# WeightAlarm.net
KiCad netlist of a schematic drawn in EAGLE
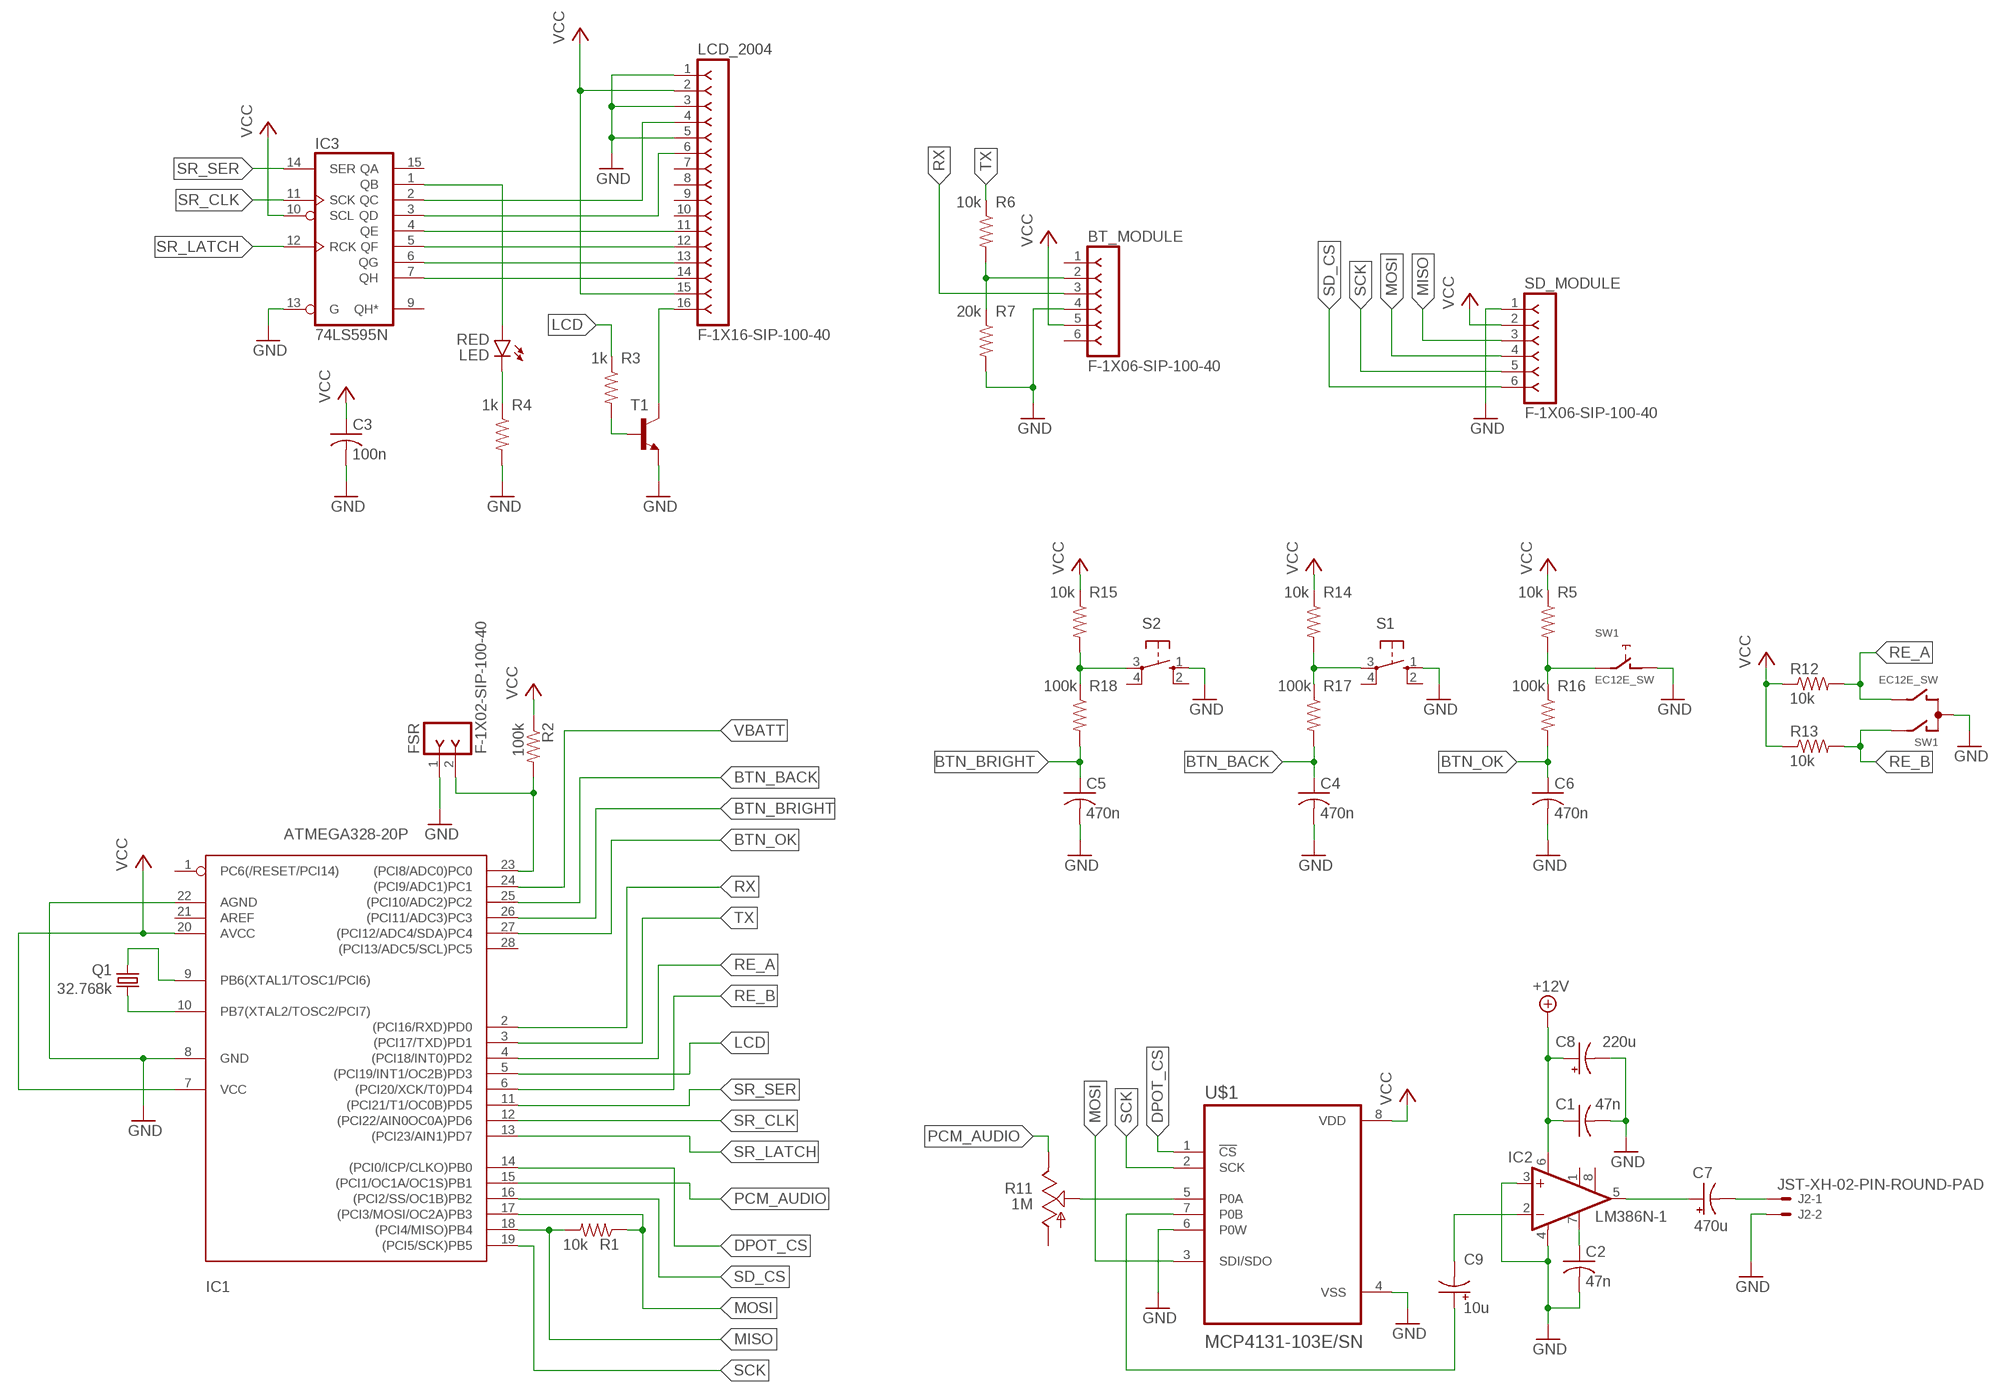
[diagram p0: schematic, sheet 1]

(export (version "E")
  (design (tool "Eeschema 10.0.6"))
  (components
    (comp (ref "BT_MODULE")
      (value "F-1X06-SIP-100-40")
      (footprint "eagle-import:SIP-100-06-40")
      (libsource (lib "eagle-import") (part "F-1X06-SIP-100-40"))
    )
    (comp (ref "C1")
      (value "47n")
      (footprint "eagle-import:C025-030X050")
      (libsource (lib "eagle-import") (part "C-US025-030X050"))
    )
    (comp (ref "C2")
      (value "47n")
      (footprint "eagle-import:C025-030X050")
      (libsource (lib "eagle-import") (part "C-US025-030X050"))
    )
    (comp (ref "C3")
      (value "100n")
      (footprint "eagle-import:C025-030X050")
      (libsource (lib "eagle-import") (part "C-US025-030X050"))
    )
    (comp (ref "C4")
      (value "470n")
      (footprint "eagle-import:C025-030X050")
      (libsource (lib "eagle-import") (part "C-US025-030X050"))
    )
    (comp (ref "C5")
      (value "470n")
      (footprint "eagle-import:C025-030X050")
      (libsource (lib "eagle-import") (part "C-US025-030X050"))
    )
    (comp (ref "C6")
      (value "470n")
      (footprint "eagle-import:C025-030X050")
      (libsource (lib "eagle-import") (part "C-US025-030X050"))
    )
    (comp (ref "C7")
      (value "470u")
      (footprint "eagle-import:E2,5-7")
      (libsource (lib "eagle-import") (part "CPOL-USE2.5-7"))
    )
    (comp (ref "C8")
      (value "220u")
      (footprint "eagle-import:E2,5-6")
      (libsource (lib "eagle-import") (part "CPOL-USE2.5-6"))
    )
    (comp (ref "C9")
      (value "10u")
      (footprint "eagle-import:E2,5-5")
      (libsource (lib "eagle-import") (part "CPOL-USE2.5-5"))
    )
    (comp (ref "FSR")
      (value "F-1X02-SIP-100-40")
      (footprint "eagle-import:SIP-100-02-40")
      (libsource (lib "eagle-import") (part "F-1X02-SIP-100-40"))
    )
    (comp (ref "IC1")
      (value "ATMEGA328-20P")
      (footprint "eagle-import:DIL28-3")
      (libsource (lib "eagle-import") (part "ATMEGA328P-20"))
    )
    (comp (ref "IC2")
      (value "LM386N-1")
      (footprint "eagle-import:DIL08")
      (libsource (lib "eagle-import") (part "LM386?-N1"))
    )
    (comp (ref "IC3")
      (value "74LS595N")
      (footprint "eagle-import:DIL16")
      (fields (field (name "SPICEPREFIX") "X"))
      (libsource (lib "eagle-import") (part "74595NLS"))
    )
    (comp (ref "J2")
      (value "JST-XH-02-PIN-ROUND-PAD")
      (footprint "eagle-import:JST-XH-02-PACKAGE-ROUND-PAD")
      (libsource (lib "eagle-import") (part "JST-XH-02-PIN-ROUND-PAD"))
    )
    (comp (ref "LCD_2004")
      (value "F-1X16-SIP-100-40")
      (footprint "eagle-import:SIP-100-16-40")
      (fields (field (name "SPICEPREFIX") "X"))
      (libsource (lib "eagle-import") (part "F-1X16-SIP-100-40"))
    )
    (comp (ref "LED")
      (value "RED")
      (footprint "eagle-import:LED5MM")
      (fields (field (name "SPICEPREFIX") "L"))
      (libsource (lib "eagle-import") (part "LED5MM"))
    )
    (comp (ref "Q1")
      (value "32.768k")
      (footprint "eagle-import:TC26V")
      (libsource (lib "eagle-import") (part "CRYSTALTC26V"))
    )
    (comp (ref "R1")
      (value "10k")
      (footprint "eagle-import:0207_7")
      (libsource (lib "eagle-import") (part "R-US_0207/7"))
    )
    (comp (ref "R2")
      (value "100k")
      (footprint "eagle-import:0207_7")
      (libsource (lib "eagle-import") (part "R-US_0207/7"))
    )
    (comp (ref "R3")
      (value "1k")
      (footprint "eagle-import:0207_7")
      (libsource (lib "eagle-import") (part "R-US_0207/7"))
    )
    (comp (ref "R4")
      (value "1k")
      (footprint "eagle-import:0207_7")
      (libsource (lib "eagle-import") (part "R-US_0207/7"))
    )
    (comp (ref "R5")
      (value "10k")
      (footprint "eagle-import:0207_7")
      (libsource (lib "eagle-import") (part "R-US_0207/7"))
    )
    (comp (ref "R6")
      (value "10k")
      (footprint "eagle-import:0207_7")
      (libsource (lib "eagle-import") (part "R-US_0207/7"))
    )
    (comp (ref "R7")
      (value "20k")
      (footprint "eagle-import:0207_7")
      (libsource (lib "eagle-import") (part "R-US_0207/7"))
    )
    (comp (ref "R11")
      (value "1M")
      (footprint "eagle-import:B25P")
      (libsource (lib "eagle-import") (part "TRIM_US-B25P"))
    )
    (comp (ref "R12")
      (value "10k")
      (footprint "eagle-import:0207_7")
      (libsource (lib "eagle-import") (part "R-US_0207/7"))
    )
    (comp (ref "R13")
      (value "10k")
      (footprint "eagle-import:0207_7")
      (libsource (lib "eagle-import") (part "R-US_0207/7"))
    )
    (comp (ref "R14")
      (value "10k")
      (footprint "eagle-import:0207_7")
      (libsource (lib "eagle-import") (part "R-US_0207/7"))
    )
    (comp (ref "R15")
      (value "10k")
      (footprint "eagle-import:0207_7")
      (libsource (lib "eagle-import") (part "R-US_0207/7"))
    )
    (comp (ref "R16")
      (value "100k")
      (footprint "eagle-import:0207_7")
      (libsource (lib "eagle-import") (part "R-US_0207/7"))
    )
    (comp (ref "R17")
      (value "100k")
      (footprint "eagle-import:0207_7")
      (libsource (lib "eagle-import") (part "R-US_0207/7"))
    )
    (comp (ref "R18")
      (value "100k")
      (footprint "eagle-import:0207_7")
      (libsource (lib "eagle-import") (part "R-US_0207/7"))
    )
    (comp (ref "S1")
      (value "10-XX")
      (footprint "eagle-import:B3F-10XX")
      (fields (field (name "MPN") "B3F-1000"))
      (libsource (lib "eagle-import") (part "10-XX"))
    )
    (comp (ref "S2")
      (value "10-XX")
      (footprint "eagle-import:B3F-10XX")
      (fields (field (name "MPN") "B3F-1000"))
      (libsource (lib "eagle-import") (part "10-XX"))
    )
    (comp (ref "SD_MODULE")
      (value "F-1X06-SIP-100-40")
      (footprint "eagle-import:SIP-100-06-40")
      (libsource (lib "eagle-import") (part "F-1X06-SIP-100-40"))
    )
    (comp (ref "SW1")
      (value "EC12E_SW")
      (footprint "eagle-import:ALPS_EC12E_SW")
      (fields (field (name "MPN") "EC12E2424407"))
      (libsource (lib "eagle-import") (part "EC12E_SW"))
    )
    (comp (ref "T1")
      (value "-NPN-TO92-EBC")
      (footprint "eagle-import:TO92-EBC")
      (fields (field (name "SPICEPREFIX") "J"))
      (libsource (lib "eagle-import") (part "-NPN-TO92-EBC"))
    )
    (comp (ref "U$1")
      (value "MCP4131-103E/SN")
      (footprint "eagle-import:SOIC127P599X175-8N")
      (fields (field (name "MF") "Microchip"))
      (libsource (lib "eagle-import") (part "MCP4131-103E/SN"))
    )
  )
  (nets
    (net (code "1") (name "+12V") (class "Default")
      (node (ref "C1") (pin "1") (pinfunction "1_1") (pintype "passive"))
      (node (ref "C8") (pin "+") (pinfunction "+_+") (pintype "passive"))
      (node (ref "IC2") (pin "6") (pinfunction "VS_6") (pintype "power_in"))
    )
    (net (code "2") (name "BTN_BACK") (class "Default")
      (node (ref "C4") (pin "1") (pinfunction "1_1") (pintype "passive"))
      (node (ref "IC1") (pin "25") (pinfunction "(PCI10/ADC2)PC2_25") (pintype "bidirectional"))
      (node (ref "R17") (pin "2") (pinfunction "2_2") (pintype "passive"))
    )
    (net (code "3") (name "BTN_BRIGHT") (class "Default")
      (node (ref "C5") (pin "1") (pinfunction "1_1") (pintype "passive"))
      (node (ref "IC1") (pin "26") (pinfunction "(PCI11/ADC3)PC3_26") (pintype "bidirectional"))
      (node (ref "R18") (pin "2") (pinfunction "2_2") (pintype "passive"))
    )
    (net (code "4") (name "BTN_OK") (class "Default")
      (node (ref "C6") (pin "1") (pinfunction "1_1") (pintype "passive"))
      (node (ref "IC1") (pin "27") (pinfunction "(PCI12/ADC4/SDA)PC4_27") (pintype "bidirectional"))
      (node (ref "R16") (pin "2") (pinfunction "2_2") (pintype "passive"))
    )
    (net (code "5") (name "DPOT_CS") (class "Default")
      (node (ref "IC1") (pin "14") (pinfunction "(PCI0/ICP/CLKO)PB0_14") (pintype "bidirectional"))
      (node (ref "U$1") (pin "1") (pinfunction "~{CS}_1") (pintype "input"))
    )
    (net (code "6") (name "GND") (class "Default")
      (node (ref "BT_MODULE") (pin "4") (pinfunction "4_4") (pintype "passive"))
      (node (ref "C1") (pin "2") (pinfunction "2_2") (pintype "passive"))
      (node (ref "C2") (pin "2") (pinfunction "2_2") (pintype "passive"))
      (node (ref "C3") (pin "2") (pinfunction "2_2") (pintype "passive"))
      (node (ref "C4") (pin "2") (pinfunction "2_2") (pintype "passive"))
      (node (ref "C5") (pin "2") (pinfunction "2_2") (pintype "passive"))
      (node (ref "C6") (pin "2") (pinfunction "2_2") (pintype "passive"))
      (node (ref "C8") (pin "-") (pinfunction "-_-") (pintype "passive"))
      (node (ref "FSR") (pin "1") (pinfunction "1_1") (pintype "passive"))
      (node (ref "IC1") (pin "22") (pinfunction "AGND_22") (pintype "bidirectional"))
      (node (ref "IC1") (pin "8") (pinfunction "GND_8") (pintype "bidirectional"))
      (node (ref "IC2") (pin "3") (pinfunction "+IN_3") (pintype "input"))
      (node (ref "IC2") (pin "4") (pinfunction "GND_4") (pintype "power_in"))
      (node (ref "IC3") (pin "13") (pinfunction "G_13") (pintype "input"))
      (node (ref "J2") (pin "2") (pinfunction "S_2") (pintype "passive"))
      (node (ref "LCD_2004") (pin "1") (pinfunction "1_1") (pintype "passive"))
      (node (ref "LCD_2004") (pin "3") (pinfunction "3_3") (pintype "passive"))
      (node (ref "LCD_2004") (pin "5") (pinfunction "5_5") (pintype "passive"))
      (node (ref "R4") (pin "2") (pinfunction "2_2") (pintype "passive"))
      (node (ref "R7") (pin "2") (pinfunction "2_2") (pintype "passive"))
      (node (ref "S1") (pin "1") (pinfunction "S_1") (pintype "passive"))
      (node (ref "S2") (pin "1") (pinfunction "S_1") (pintype "passive"))
      (node (ref "SD_MODULE") (pin "1") (pinfunction "1_1") (pintype "passive"))
      (node (ref "SW1") (pin "C") (pinfunction "C_C") (pintype "passive"))
      (node (ref "SW1") (pin "D") (pinfunction "1_D") (pintype "passive"))
      (node (ref "T1") (pin "E") (pinfunction "E_E") (pintype "passive"))
      (node (ref "U$1") (pin "4") (pinfunction "VSS_4") (pintype "power_in"))
      (node (ref "U$1") (pin "6") (pinfunction "P0W_6") (pintype "bidirectional"))
    )
    (net (code "7") (name "LCD") (class "Default")
      (node (ref "IC1") (pin "5") (pinfunction "(PCI19/INT1/OC2B)PD3_5") (pintype "bidirectional"))
      (node (ref "R3") (pin "1") (pinfunction "1_1") (pintype "passive"))
    )
    (net (code "8") (name "MISO") (class "Default")
      (node (ref "IC1") (pin "18") (pinfunction "(PCI4/MISO)PB4_18") (pintype "bidirectional"))
      (node (ref "R1") (pin "2") (pinfunction "2_2") (pintype "passive"))
      (node (ref "SD_MODULE") (pin "3") (pinfunction "3_3") (pintype "passive"))
    )
    (net (code "9") (name "MOSI") (class "Default")
      (node (ref "IC1") (pin "17") (pinfunction "(PCI3/MOSI/OC2A)PB3_17") (pintype "bidirectional"))
      (node (ref "R1") (pin "1") (pinfunction "1_1") (pintype "passive"))
      (node (ref "SD_MODULE") (pin "4") (pinfunction "4_4") (pintype "passive"))
      (node (ref "U$1") (pin "3") (pinfunction "SDI/SDO_3") (pintype "bidirectional"))
    )
    (net (code "10") (name "Net-(IC1-(PCI8{slash}ADC0)PC0)") (class "Default")
      (node (ref "FSR") (pin "2") (pinfunction "2_2") (pintype "passive"))
      (node (ref "IC1") (pin "23") (pinfunction "(PCI8/ADC0)PC0_23") (pintype "bidirectional"))
      (node (ref "R2") (pin "2") (pinfunction "2_2") (pintype "passive"))
    )
    (net (code "11") (name "Net-(IC1-PB6(XTAL1{slash}TOSC1{slash}PCI6))") (class "Default")
      (node (ref "IC1") (pin "9") (pinfunction "PB6(XTAL1/TOSC1/PCI6)_9") (pintype "bidirectional"))
      (node (ref "Q1") (pin "2") (pinfunction "2_2") (pintype "passive"))
    )
    (net (code "12") (name "Net-(IC1-PB7(XTAL2{slash}TOSC2{slash}PCI7))") (class "Default")
      (node (ref "IC1") (pin "10") (pinfunction "PB7(XTAL2/TOSC2/PCI7)_10") (pintype "bidirectional"))
      (node (ref "Q1") (pin "1") (pinfunction "1_1") (pintype "passive"))
    )
    (net (code "13") (name "Net-(IC2--IN)") (class "Default")
      (node (ref "C9") (pin "-") (pinfunction "-_-") (pintype "passive"))
      (node (ref "IC2") (pin "2") (pinfunction "-IN_2") (pintype "input"))
    )
    (net (code "14") (name "Net-(IC2-BYPASS)") (class "Default")
      (node (ref "C2") (pin "1") (pinfunction "1_1") (pintype "passive"))
      (node (ref "IC2") (pin "7") (pinfunction "BYPASS_7") (pintype "passive"))
    )
    (net (code "15") (name "Net-(IC2-OUT)") (class "Default")
      (node (ref "C7") (pin "+") (pinfunction "+_+") (pintype "passive"))
      (node (ref "IC2") (pin "5") (pinfunction "OUT_5") (pintype "output"))
    )
    (net (code "16") (name "Net-(IC3A-QB)") (class "Default")
      (node (ref "IC3") (pin "1") (pinfunction "QB_1") (pintype "tri_state"))
      (node (ref "LED") (pin "A") (pinfunction "A_A") (pintype "passive"))
    )
    (net (code "17") (name "Net-(IC3A-QC)") (class "Default")
      (node (ref "IC3") (pin "2") (pinfunction "QC_2") (pintype "tri_state"))
      (node (ref "LCD_2004") (pin "4") (pinfunction "4_4") (pintype "passive"))
    )
    (net (code "18") (name "Net-(IC3A-QD)") (class "Default")
      (node (ref "IC3") (pin "3") (pinfunction "QD_3") (pintype "tri_state"))
      (node (ref "LCD_2004") (pin "6") (pinfunction "6_6") (pintype "passive"))
    )
    (net (code "19") (name "Net-(IC3A-QE)") (class "Default")
      (node (ref "IC3") (pin "4") (pinfunction "QE_4") (pintype "tri_state"))
      (node (ref "LCD_2004") (pin "11") (pinfunction "11_11") (pintype "passive"))
    )
    (net (code "20") (name "Net-(IC3A-QF)") (class "Default")
      (node (ref "IC3") (pin "5") (pinfunction "QF_5") (pintype "tri_state"))
      (node (ref "LCD_2004") (pin "12") (pinfunction "12_12") (pintype "passive"))
    )
    (net (code "21") (name "Net-(IC3A-QG)") (class "Default")
      (node (ref "IC3") (pin "6") (pinfunction "QG_6") (pintype "tri_state"))
      (node (ref "LCD_2004") (pin "13") (pinfunction "13_13") (pintype "passive"))
    )
    (net (code "22") (name "Net-(IC3A-QH)") (class "Default")
      (node (ref "IC3") (pin "7") (pinfunction "QH_7") (pintype "tri_state"))
      (node (ref "LCD_2004") (pin "14") (pinfunction "14_14") (pintype "passive"))
    )
    (net (code "23") (name "Net-(J2A-S)") (class "Default")
      (node (ref "C7") (pin "-") (pinfunction "-_-") (pintype "passive"))
      (node (ref "J2") (pin "1") (pinfunction "S_1") (pintype "passive"))
    )
    (net (code "24") (name "Net-(LCD_2004-Pad16)") (class "Default")
      (node (ref "LCD_2004") (pin "16") (pinfunction "16_16") (pintype "passive"))
      (node (ref "T1") (pin "C") (pinfunction "C_C") (pintype "passive"))
    )
    (net (code "25") (name "Net-(LED-C)") (class "Default")
      (node (ref "LED") (pin "K") (pinfunction "C_K") (pintype "passive"))
      (node (ref "R4") (pin "1") (pinfunction "1_1") (pintype "passive"))
    )
    (net (code "26") (name "Net-(R3-Pad2)") (class "Default")
      (node (ref "R3") (pin "2") (pinfunction "2_2") (pintype "passive"))
      (node (ref "T1") (pin "B") (pinfunction "B_B") (pintype "passive"))
    )
    (net (code "27") (name "Net-(S1-P)") (class "Default")
      (node (ref "R14") (pin "2") (pinfunction "2_2") (pintype "passive"))
      (node (ref "R17") (pin "1") (pinfunction "1_1") (pintype "passive"))
      (node (ref "S1") (pin "3") (pinfunction "P_3") (pintype "passive"))
    )
    (net (code "28") (name "Net-(S2-P)") (class "Default")
      (node (ref "R15") (pin "2") (pinfunction "2_2") (pintype "passive"))
      (node (ref "R18") (pin "1") (pinfunction "1_1") (pintype "passive"))
      (node (ref "S2") (pin "3") (pinfunction "P_3") (pintype "passive"))
    )
    (net (code "29") (name "Net-(SW1B-2)") (class "Default")
      (node (ref "R16") (pin "1") (pinfunction "1_1") (pintype "passive"))
      (node (ref "R5") (pin "2") (pinfunction "2_2") (pintype "passive"))
      (node (ref "SW1") (pin "E") (pinfunction "2_E") (pintype "passive"))
    )
    (net (code "30") (name "Net-(U$1-P0A)") (class "Default")
      (node (ref "R11") (pin "S") (pinfunction "S_S") (pintype "passive"))
      (node (ref "U$1") (pin "5") (pinfunction "P0A_5") (pintype "bidirectional"))
    )
    (net (code "31") (name "Net-(U$1-P0B)") (class "Default")
      (node (ref "C9") (pin "+") (pinfunction "+_+") (pintype "passive"))
      (node (ref "U$1") (pin "7") (pinfunction "P0B_7") (pintype "bidirectional"))
    )
    (net (code "32") (name "PCM_AUDIO") (class "Default")
      (node (ref "IC1") (pin "15") (pinfunction "(PCI1/OC1A/OC1S)PB1_15") (pintype "bidirectional"))
      (node (ref "R11") (pin "E") (pinfunction "E_E") (pintype "passive"))
    )
    (net (code "33") (name "RE_A") (class "Default")
      (node (ref "IC1") (pin "4") (pinfunction "(PCI18/INT0)PD2_4") (pintype "bidirectional"))
      (node (ref "R12") (pin "2") (pinfunction "2_2") (pintype "passive"))
      (node (ref "SW1") (pin "B") (pinfunction "B_B") (pintype "passive"))
    )
    (net (code "34") (name "RE_B") (class "Default")
      (node (ref "IC1") (pin "6") (pinfunction "(PCI20/XCK/T0)PD4_6") (pintype "bidirectional"))
      (node (ref "R13") (pin "2") (pinfunction "2_2") (pintype "passive"))
      (node (ref "SW1") (pin "A") (pinfunction "A_A") (pintype "passive"))
    )
    (net (code "35") (name "RX") (class "Default")
      (node (ref "BT_MODULE") (pin "3") (pinfunction "3_3") (pintype "passive"))
      (node (ref "IC1") (pin "2") (pinfunction "(PCI16/RXD)PD0_2") (pintype "bidirectional"))
    )
    (net (code "36") (name "SCK") (class "Default")
      (node (ref "IC1") (pin "19") (pinfunction "(PCI5/SCK)PB5_19") (pintype "bidirectional"))
      (node (ref "SD_MODULE") (pin "5") (pinfunction "5_5") (pintype "passive"))
      (node (ref "U$1") (pin "2") (pinfunction "SCK_2") (pintype "input"))
    )
    (net (code "37") (name "SD_CS") (class "Default")
      (node (ref "IC1") (pin "16") (pinfunction "(PCI2/SS/OC1B)PB2_16") (pintype "bidirectional"))
      (node (ref "SD_MODULE") (pin "6") (pinfunction "6_6") (pintype "passive"))
    )
    (net (code "38") (name "SR_CLK") (class "Default")
      (node (ref "IC1") (pin "12") (pinfunction "(PCI22/AIN0OC0A)PD6_12") (pintype "bidirectional"))
      (node (ref "IC3") (pin "11") (pinfunction "SCK_11") (pintype "input"))
    )
    (net (code "39") (name "SR_LATCH") (class "Default")
      (node (ref "IC1") (pin "13") (pinfunction "(PCI23/AIN1)PD7_13") (pintype "bidirectional"))
      (node (ref "IC3") (pin "12") (pinfunction "RCK_12") (pintype "input"))
    )
    (net (code "40") (name "SR_SER") (class "Default")
      (node (ref "IC1") (pin "11") (pinfunction "(PCI21/T1/OC0B)PD5_11") (pintype "bidirectional"))
      (node (ref "IC3") (pin "14") (pinfunction "SER_14") (pintype "input"))
    )
    (net (code "41") (name "TX") (class "Default")
      (node (ref "BT_MODULE") (pin "2") (pinfunction "2_2") (pintype "passive"))
      (node (ref "IC1") (pin "3") (pinfunction "(PCI17/TXD)PD1_3") (pintype "bidirectional"))
      (node (ref "R6") (pin "1") (pinfunction "1_1") (pintype "passive"))
      (node (ref "R6") (pin "2") (pinfunction "2_2") (pintype "passive"))
      (node (ref "R7") (pin "1") (pinfunction "1_1") (pintype "passive"))
    )
    (net (code "42") (name "VBATT") (class "Default")
      (node (ref "IC1") (pin "24") (pinfunction "(PCI9/ADC1)PC1_24") (pintype "bidirectional"))
    )
    (net (code "43") (name "VCC") (class "Default")
      (node (ref "BT_MODULE") (pin "5") (pinfunction "5_5") (pintype "passive"))
      (node (ref "C3") (pin "1") (pinfunction "1_1") (pintype "passive"))
      (node (ref "IC1") (pin "20") (pinfunction "AVCC_20") (pintype "bidirectional"))
      (node (ref "IC1") (pin "7") (pinfunction "VCC_7") (pintype "bidirectional"))
      (node (ref "IC3") (pin "10") (pinfunction "SCL_10") (pintype "input"))
      (node (ref "LCD_2004") (pin "15") (pinfunction "15_15") (pintype "passive"))
      (node (ref "LCD_2004") (pin "2") (pinfunction "2_2") (pintype "passive"))
      (node (ref "R12") (pin "1") (pinfunction "1_1") (pintype "passive"))
      (node (ref "R13") (pin "1") (pinfunction "1_1") (pintype "passive"))
      (node (ref "R14") (pin "1") (pinfunction "1_1") (pintype "passive"))
      (node (ref "R15") (pin "1") (pinfunction "1_1") (pintype "passive"))
      (node (ref "R2") (pin "1") (pinfunction "1_1") (pintype "passive"))
      (node (ref "R5") (pin "1") (pinfunction "1_1") (pintype "passive"))
      (node (ref "SD_MODULE") (pin "2") (pinfunction "2_2") (pintype "passive"))
      (node (ref "U$1") (pin "8") (pinfunction "VDD_8") (pintype "power_in"))
    )
    (net (code "44") (name "unconnected-(BT_MODULE-Pad1)") (class "Default")
      (node (ref "BT_MODULE") (pin "1") (pinfunction "1_1") (pintype "passive"))
    )
    (net (code "45") (name "unconnected-(BT_MODULE-Pad6)") (class "Default")
      (node (ref "BT_MODULE") (pin "6") (pinfunction "6_6") (pintype "passive"))
    )
    (net (code "46") (name "unconnected-(IC1-(PCI13{slash}ADC5{slash}SCL)PC5-Pad28)") (class "Default")
      (node (ref "IC1") (pin "28") (pinfunction "(PCI13/ADC5/SCL)PC5_28") (pintype "bidirectional"))
    )
    (net (code "47") (name "unconnected-(IC1-AREF-Pad21)") (class "Default")
      (node (ref "IC1") (pin "21") (pinfunction "AREF_21") (pintype "bidirectional"))
    )
    (net (code "48") (name "unconnected-(IC1-PC6({slash}RESET{slash}PCI14)-Pad1)") (class "Default")
      (node (ref "IC1") (pin "1") (pinfunction "PC6(/RESET/PCI14)_1") (pintype "bidirectional"))
    )
    (net (code "49") (name "unconnected-(IC2-GAIN-Pad1)") (class "Default")
      (node (ref "IC2") (pin "1") (pinfunction "GAIN_1") (pintype "passive"))
    )
    (net (code "50") (name "unconnected-(IC2-GAIN-Pad8)") (class "Default")
      (node (ref "IC2") (pin "8") (pinfunction "GAIN_8") (pintype "passive"))
    )
    (net (code "51") (name "unconnected-(IC3A-QA-Pad15)") (class "Default")
      (node (ref "IC3") (pin "15") (pinfunction "QA_15") (pintype "tri_state"))
    )
    (net (code "52") (name "unconnected-(IC3A-QH*-Pad9)") (class "Default")
      (node (ref "IC3") (pin "9") (pinfunction "QH*_9") (pintype "tri_state"))
    )
    (net (code "53") (name "unconnected-(LCD_2004-Pad7)") (class "Default")
      (node (ref "LCD_2004") (pin "7") (pinfunction "7_7") (pintype "passive"))
    )
    (net (code "54") (name "unconnected-(LCD_2004-Pad8)") (class "Default")
      (node (ref "LCD_2004") (pin "8") (pinfunction "8_8") (pintype "passive"))
    )
    (net (code "55") (name "unconnected-(LCD_2004-Pad9)") (class "Default")
      (node (ref "LCD_2004") (pin "9") (pinfunction "9_9") (pintype "passive"))
    )
    (net (code "56") (name "unconnected-(LCD_2004-Pad10)") (class "Default")
      (node (ref "LCD_2004") (pin "10") (pinfunction "10_10") (pintype "passive"))
    )
    (net (code "57") (name "unconnected-(R11-PadA)") (class "Default")
      (node (ref "R11") (pin "A") (pinfunction "A_A") (pintype "passive"))
    )
    (net (code "58") (name "unconnected-(S1-P1-Pad4)") (class "Default")
      (node (ref "S1") (pin "4") (pinfunction "P1_4") (pintype "passive"))
    )
    (net (code "59") (name "unconnected-(S1-S1-Pad2)") (class "Default")
      (node (ref "S1") (pin "2") (pinfunction "S1_2") (pintype "passive"))
    )
    (net (code "60") (name "unconnected-(S2-P1-Pad4)") (class "Default")
      (node (ref "S2") (pin "4") (pinfunction "P1_4") (pintype "passive"))
    )
    (net (code "61") (name "unconnected-(S2-S1-Pad2)") (class "Default")
      (node (ref "S2") (pin "2") (pinfunction "S1_2") (pintype "passive"))
    )
  )
)
